# TinyBattery_I2C_V1.net
KiCad netlist of a schematic drawn in EAGLE
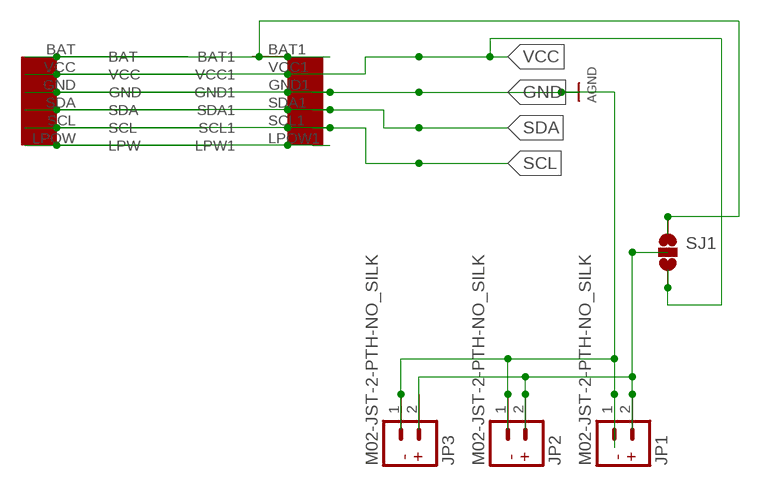
[diagram p0: schematic, sheet 1]

(export (version "E")
  (design (tool "Eeschema 10.0.6"))
  (components
    (comp (ref "JP1")
      (value "M02-JST-2-PTH-NO_SILK")
      (footprint "eagle-import:JST-2-PTH-NS")
      (libsource (lib "eagle-import") (part "M02-JST-2-PTH-NO_SILK"))
    )
    (comp (ref "JP2")
      (value "M02-JST-2-PTH-NO_SILK")
      (footprint "eagle-import:JST-2-PTH-NS")
      (libsource (lib "eagle-import") (part "M02-JST-2-PTH-NO_SILK"))
    )
    (comp (ref "JP3")
      (value "M02-JST-2-PTH-NO_SILK")
      (footprint "eagle-import:JST-2-PTH-NS")
      (libsource (lib "eagle-import") (part "M02-JST-2-PTH-NO_SILK"))
    )
    (comp (ref "SJ1")
      (value "SOLDERJUMPER_2WAYPASTE1&2")
      (footprint "eagle-import:SJ_3_PASTE1&2")
      (libsource (lib "eagle-import") (part "SOLDERJUMPER_2WAYPASTE1&2"))
    )
    (comp (ref "U$1")
      (value "EZ-I2CHEADERV1")
      (footprint "eagle-import:EZ-I2CHEADERV1")
      (libsource (lib "eagle-import") (part "EZ-I2CHEADERV1"))
    )
  )
  (nets
    (net (code "1") (name "GND") (class "Default")
      (node (ref "JP1") (pin "1") (pinfunction "1_1") (pintype "passive"))
      (node (ref "JP2") (pin "1") (pinfunction "1_1") (pintype "passive"))
      (node (ref "JP3") (pin "1") (pinfunction "1_1") (pintype "passive"))
      (node (ref "U$1") (pin "GND") (pinfunction "GND_GND") (pintype "bidirectional"))
      (node (ref "U$1") (pin "GND1") (pinfunction "GND1_GND1") (pintype "bidirectional"))
    )
    (net (code "2") (name "Net-(JP1-Pad2)") (class "Default")
      (node (ref "JP1") (pin "2") (pinfunction "2_2") (pintype "passive"))
      (node (ref "JP2") (pin "2") (pinfunction "2_2") (pintype "passive"))
      (node (ref "JP3") (pin "2") (pinfunction "2_2") (pintype "passive"))
      (node (ref "SJ1") (pin "2") (pinfunction "2_2") (pintype "passive"))
    )
    (net (code "3") (name "Net-(SJ1-Pad1)") (class "Default")
      (node (ref "SJ1") (pin "1") (pinfunction "1_1") (pintype "passive"))
      (node (ref "U$1") (pin "BAT") (pinfunction "BAT_BAT") (pintype "bidirectional"))
      (node (ref "U$1") (pin "BAT1") (pinfunction "BAT1_BAT1") (pintype "bidirectional"))
    )
    (net (code "4") (name "Net-(U$1-LPW)") (class "Default")
      (node (ref "U$1") (pin "LPOW") (pinfunction "LPW_LPOW") (pintype "bidirectional"))
      (node (ref "U$1") (pin "LPOW1") (pinfunction "LPW1_LPOW1") (pintype "bidirectional"))
    )
    (net (code "5") (name "SCL") (class "Default")
      (node (ref "U$1") (pin "SCL") (pinfunction "SCL_SCL") (pintype "bidirectional"))
      (node (ref "U$1") (pin "SCL1") (pinfunction "SCL1_SCL1") (pintype "bidirectional"))
    )
    (net (code "6") (name "SDA") (class "Default")
      (node (ref "U$1") (pin "SDA") (pinfunction "SDA_SDA") (pintype "bidirectional"))
      (node (ref "U$1") (pin "SDA1") (pinfunction "SDA1_SDA1") (pintype "bidirectional"))
    )
    (net (code "7") (name "VCC") (class "Default")
      (node (ref "SJ1") (pin "3") (pinfunction "3_3") (pintype "passive"))
      (node (ref "U$1") (pin "VCC") (pinfunction "VCC_VCC") (pintype "bidirectional"))
      (node (ref "U$1") (pin "VCC1") (pinfunction "VCC1_VCC1") (pintype "bidirectional"))
    )
  )
)
